# PATA_Breakout_Sequencer.net
KiCad netlist of a schematic drawn in EAGLE
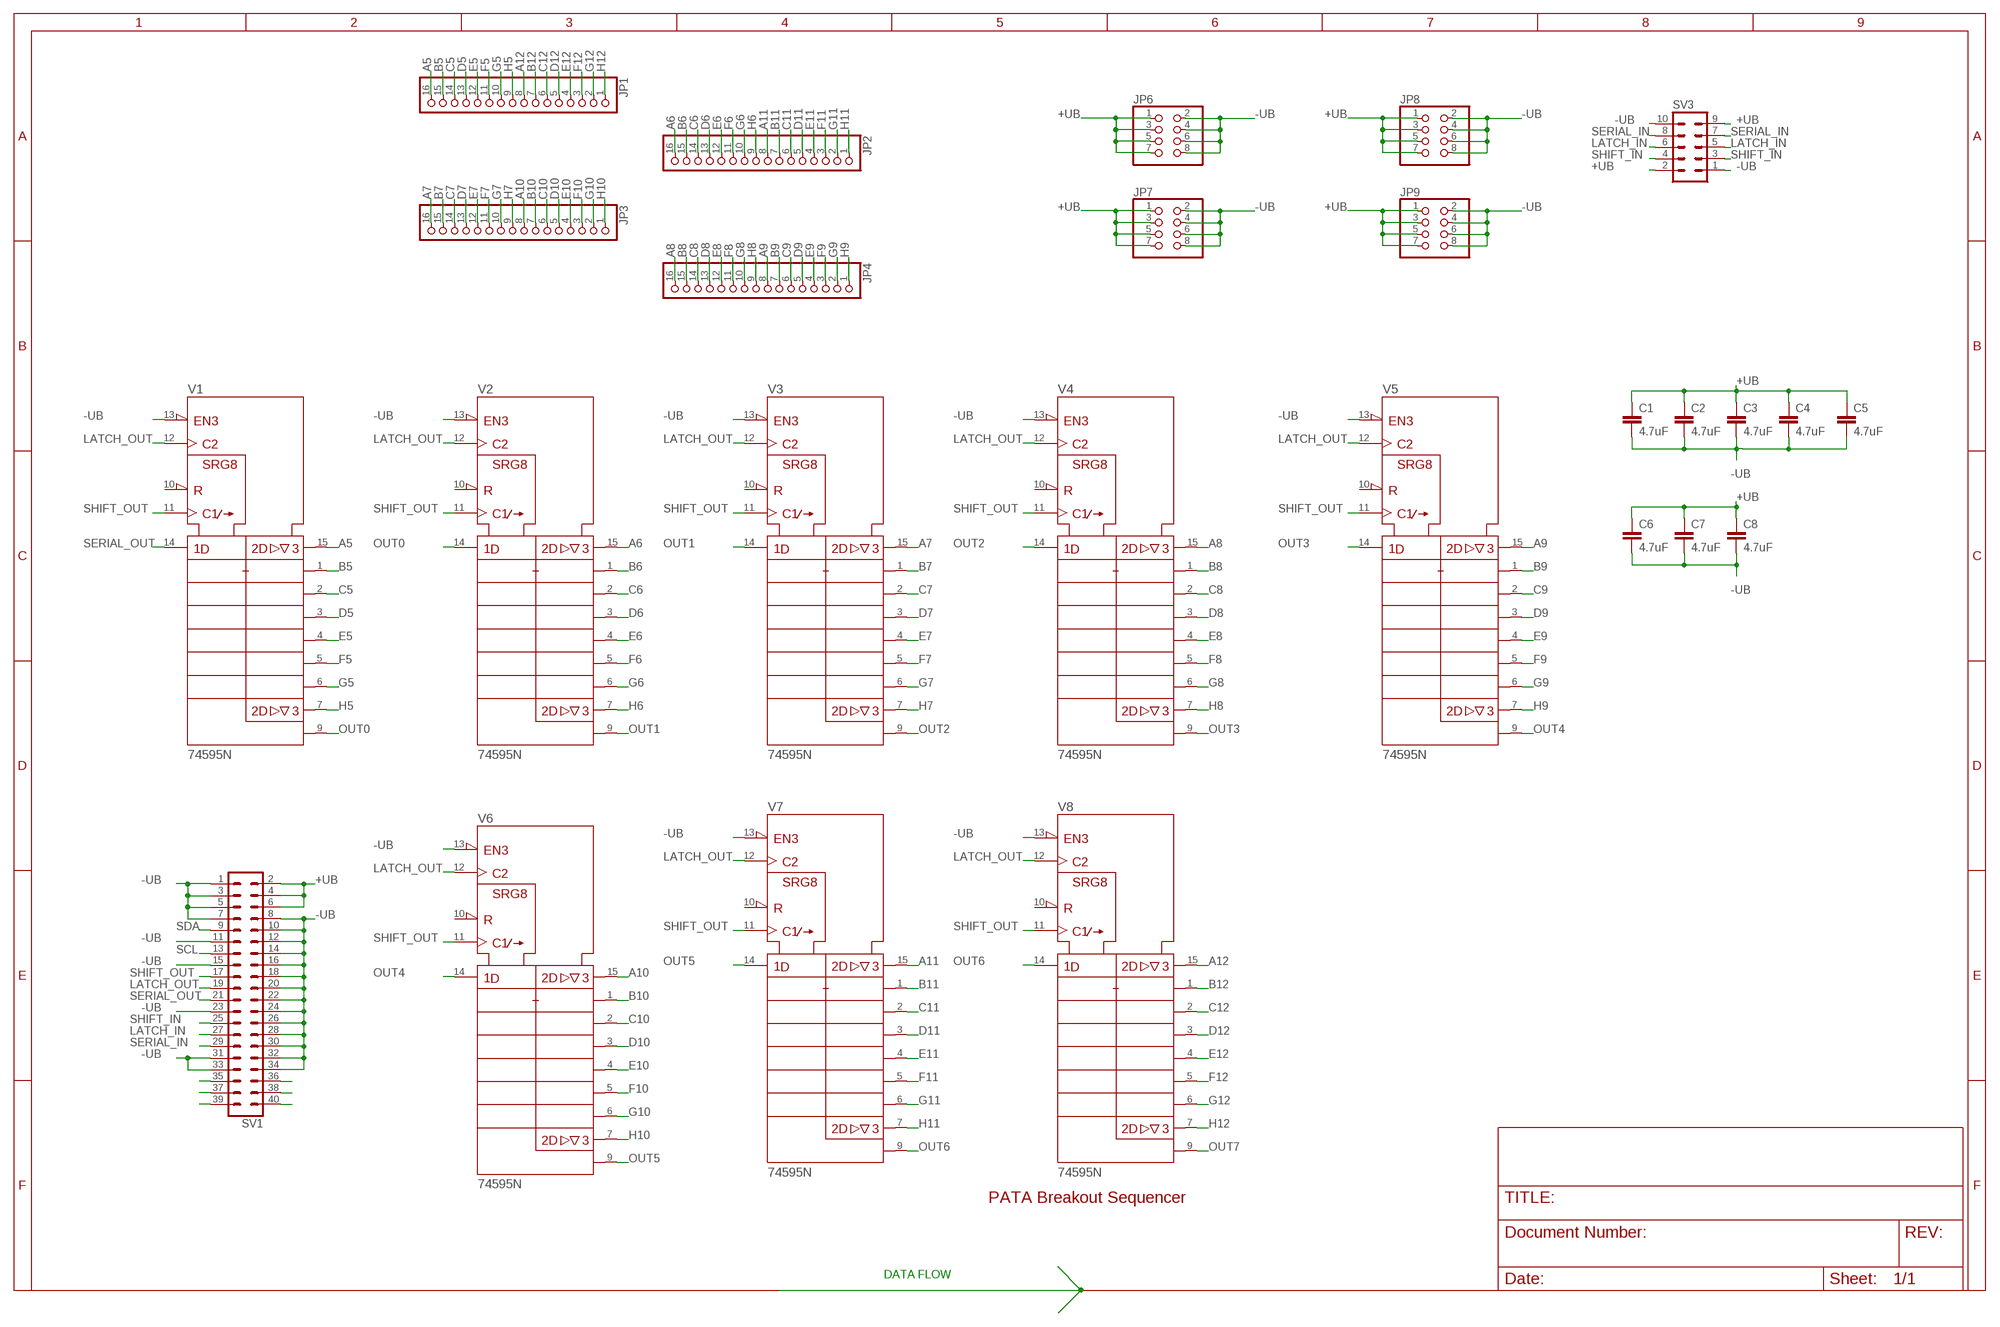
[diagram p0: schematic, sheet 1]

(export (version "E")
  (design (tool "Eeschema 10.0.6"))
  (components
    (comp (ref "C1")
      (value "4.7uF")
      (footprint "eagle-import:C050-024X044")
      (libsource (lib "eagle-import") (part "C-EU050-024X044"))
    )
    (comp (ref "C2")
      (value "4.7uF")
      (footprint "eagle-import:C050-024X044")
      (libsource (lib "eagle-import") (part "C-EU050-024X044"))
    )
    (comp (ref "C3")
      (value "4.7uF")
      (footprint "eagle-import:C050-024X044")
      (libsource (lib "eagle-import") (part "C-EU050-024X044"))
    )
    (comp (ref "C4")
      (value "4.7uF")
      (footprint "eagle-import:C050-024X044")
      (libsource (lib "eagle-import") (part "C-EU050-024X044"))
    )
    (comp (ref "C5")
      (value "4.7uF")
      (footprint "eagle-import:C050-024X044")
      (libsource (lib "eagle-import") (part "C-EU050-024X044"))
    )
    (comp (ref "C6")
      (value "4.7uF")
      (footprint "eagle-import:C050-024X044")
      (libsource (lib "eagle-import") (part "C-EU050-024X044"))
    )
    (comp (ref "C7")
      (value "4.7uF")
      (footprint "eagle-import:C050-024X044")
      (libsource (lib "eagle-import") (part "C-EU050-024X044"))
    )
    (comp (ref "C8")
      (value "4.7uF")
      (footprint "eagle-import:C050-024X044")
      (libsource (lib "eagle-import") (part "C-EU050-024X044"))
    )
    (comp (ref "JP1")
      (value "PINHD-1X16")
      (footprint "eagle-import:1X16")
      (libsource (lib "eagle-import") (part "PINHD-1X16"))
    )
    (comp (ref "JP2")
      (value "PINHD-1X16")
      (footprint "eagle-import:1X16")
      (libsource (lib "eagle-import") (part "PINHD-1X16"))
    )
    (comp (ref "JP3")
      (value "PINHD-1X16")
      (footprint "eagle-import:1X16")
      (libsource (lib "eagle-import") (part "PINHD-1X16"))
    )
    (comp (ref "JP4")
      (value "PINHD-1X16")
      (footprint "eagle-import:1X16")
      (libsource (lib "eagle-import") (part "PINHD-1X16"))
    )
    (comp (ref "JP6")
      (value "PINHD-2X4")
      (footprint "eagle-import:2X04")
      (libsource (lib "eagle-import") (part "PINHD-2X4"))
    )
    (comp (ref "JP7")
      (value "PINHD-2X4")
      (footprint "eagle-import:2X04")
      (libsource (lib "eagle-import") (part "PINHD-2X4"))
    )
    (comp (ref "JP8")
      (value "PINHD-2X4")
      (footprint "eagle-import:2X04")
      (libsource (lib "eagle-import") (part "PINHD-2X4"))
    )
    (comp (ref "JP9")
      (value "PINHD-2X4")
      (footprint "eagle-import:2X04")
      (libsource (lib "eagle-import") (part "PINHD-2X4"))
    )
    (comp (ref "SV1")
      (value "MA20-2")
      (footprint "eagle-import:MA20-2")
      (libsource (lib "eagle-import") (part "MA20-2"))
    )
    (comp (ref "SV3")
      (value "MA05-2")
      (footprint "eagle-import:MA05-2")
      (libsource (lib "eagle-import") (part "MA05-2"))
    )
    (comp (ref "V1")
      (value "74595N")
      (footprint "eagle-import:DIL16")
      (libsource (lib "eagle-import") (part "74595N"))
    )
    (comp (ref "V2")
      (value "74595N")
      (footprint "eagle-import:DIL16")
      (libsource (lib "eagle-import") (part "74595N"))
    )
    (comp (ref "V3")
      (value "74595N")
      (footprint "eagle-import:DIL16")
      (libsource (lib "eagle-import") (part "74595N"))
    )
    (comp (ref "V4")
      (value "74595N")
      (footprint "eagle-import:DIL16")
      (libsource (lib "eagle-import") (part "74595N"))
    )
    (comp (ref "V5")
      (value "74595N")
      (footprint "eagle-import:DIL16")
      (libsource (lib "eagle-import") (part "74595N"))
    )
    (comp (ref "V6")
      (value "74595N")
      (footprint "eagle-import:DIL16")
      (libsource (lib "eagle-import") (part "74595N"))
    )
    (comp (ref "V7")
      (value "74595N")
      (footprint "eagle-import:DIL16")
      (libsource (lib "eagle-import") (part "74595N"))
    )
    (comp (ref "V8")
      (value "74595N")
      (footprint "eagle-import:DIL16")
      (libsource (lib "eagle-import") (part "74595N"))
    )
  )
  (nets
    (net (code "1") (name "/+UB") (class "Default")
      (node (ref "C1") (pin "1") (pinfunction "1_1") (pintype "passive"))
      (node (ref "C2") (pin "1") (pinfunction "1_1") (pintype "passive"))
      (node (ref "C3") (pin "1") (pinfunction "1_1") (pintype "passive"))
      (node (ref "C4") (pin "1") (pinfunction "1_1") (pintype "passive"))
      (node (ref "C5") (pin "1") (pinfunction "1_1") (pintype "passive"))
      (node (ref "C6") (pin "1") (pinfunction "1_1") (pintype "passive"))
      (node (ref "C7") (pin "1") (pinfunction "1_1") (pintype "passive"))
      (node (ref "C8") (pin "1") (pinfunction "1_1") (pintype "passive"))
      (node (ref "JP6") (pin "1") (pinfunction "1_1") (pintype "passive"))
      (node (ref "JP6") (pin "3") (pinfunction "3_3") (pintype "passive"))
      (node (ref "JP6") (pin "5") (pinfunction "5_5") (pintype "passive"))
      (node (ref "JP6") (pin "7") (pinfunction "7_7") (pintype "passive"))
      (node (ref "JP7") (pin "1") (pinfunction "1_1") (pintype "passive"))
      (node (ref "JP7") (pin "3") (pinfunction "3_3") (pintype "passive"))
      (node (ref "JP7") (pin "5") (pinfunction "5_5") (pintype "passive"))
      (node (ref "JP7") (pin "7") (pinfunction "7_7") (pintype "passive"))
      (node (ref "JP8") (pin "1") (pinfunction "1_1") (pintype "passive"))
      (node (ref "JP8") (pin "3") (pinfunction "3_3") (pintype "passive"))
      (node (ref "JP8") (pin "5") (pinfunction "5_5") (pintype "passive"))
      (node (ref "JP8") (pin "7") (pinfunction "7_7") (pintype "passive"))
      (node (ref "JP9") (pin "1") (pinfunction "1_1") (pintype "passive"))
      (node (ref "JP9") (pin "3") (pinfunction "3_3") (pintype "passive"))
      (node (ref "JP9") (pin "5") (pinfunction "5_5") (pintype "passive"))
      (node (ref "JP9") (pin "7") (pinfunction "7_7") (pintype "passive"))
      (node (ref "SV1") (pin "2") (pinfunction "2_2") (pintype "passive"))
      (node (ref "SV1") (pin "4") (pinfunction "4_4") (pintype "passive"))
      (node (ref "SV1") (pin "6") (pinfunction "6_6") (pintype "passive"))
      (node (ref "SV3") (pin "2") (pinfunction "2_2") (pintype "passive"))
      (node (ref "SV3") (pin "9") (pinfunction "9_9") (pintype "passive"))
    )
    (net (code "2") (name "/-UB") (class "Default")
      (node (ref "C1") (pin "2") (pinfunction "2_2") (pintype "passive"))
      (node (ref "C2") (pin "2") (pinfunction "2_2") (pintype "passive"))
      (node (ref "C3") (pin "2") (pinfunction "2_2") (pintype "passive"))
      (node (ref "C4") (pin "2") (pinfunction "2_2") (pintype "passive"))
      (node (ref "C5") (pin "2") (pinfunction "2_2") (pintype "passive"))
      (node (ref "C6") (pin "2") (pinfunction "2_2") (pintype "passive"))
      (node (ref "C7") (pin "2") (pinfunction "2_2") (pintype "passive"))
      (node (ref "C8") (pin "2") (pinfunction "2_2") (pintype "passive"))
      (node (ref "JP6") (pin "2") (pinfunction "2_2") (pintype "passive"))
      (node (ref "JP6") (pin "4") (pinfunction "4_4") (pintype "passive"))
      (node (ref "JP6") (pin "6") (pinfunction "6_6") (pintype "passive"))
      (node (ref "JP6") (pin "8") (pinfunction "8_8") (pintype "passive"))
      (node (ref "JP7") (pin "2") (pinfunction "2_2") (pintype "passive"))
      (node (ref "JP7") (pin "4") (pinfunction "4_4") (pintype "passive"))
      (node (ref "JP7") (pin "6") (pinfunction "6_6") (pintype "passive"))
      (node (ref "JP7") (pin "8") (pinfunction "8_8") (pintype "passive"))
      (node (ref "JP8") (pin "2") (pinfunction "2_2") (pintype "passive"))
      (node (ref "JP8") (pin "4") (pinfunction "4_4") (pintype "passive"))
      (node (ref "JP8") (pin "6") (pinfunction "6_6") (pintype "passive"))
      (node (ref "JP8") (pin "8") (pinfunction "8_8") (pintype "passive"))
      (node (ref "JP9") (pin "2") (pinfunction "2_2") (pintype "passive"))
      (node (ref "JP9") (pin "4") (pinfunction "4_4") (pintype "passive"))
      (node (ref "JP9") (pin "6") (pinfunction "6_6") (pintype "passive"))
      (node (ref "JP9") (pin "8") (pinfunction "8_8") (pintype "passive"))
      (node (ref "SV1") (pin "1") (pinfunction "1_1") (pintype "passive"))
      (node (ref "SV1") (pin "10") (pinfunction "10_10") (pintype "passive"))
      (node (ref "SV1") (pin "11") (pinfunction "11_11") (pintype "passive"))
      (node (ref "SV1") (pin "12") (pinfunction "12_12") (pintype "passive"))
      (node (ref "SV1") (pin "14") (pinfunction "14_14") (pintype "passive"))
      (node (ref "SV1") (pin "15") (pinfunction "15_15") (pintype "passive"))
      (node (ref "SV1") (pin "16") (pinfunction "16_16") (pintype "passive"))
      (node (ref "SV1") (pin "18") (pinfunction "18_18") (pintype "passive"))
      (node (ref "SV1") (pin "20") (pinfunction "20_20") (pintype "passive"))
      (node (ref "SV1") (pin "22") (pinfunction "22_22") (pintype "passive"))
      (node (ref "SV1") (pin "23") (pinfunction "23_23") (pintype "passive"))
      (node (ref "SV1") (pin "24") (pinfunction "24_24") (pintype "passive"))
      (node (ref "SV1") (pin "26") (pinfunction "26_26") (pintype "passive"))
      (node (ref "SV1") (pin "28") (pinfunction "28_28") (pintype "passive"))
      (node (ref "SV1") (pin "3") (pinfunction "3_3") (pintype "passive"))
      (node (ref "SV1") (pin "30") (pinfunction "30_30") (pintype "passive"))
      (node (ref "SV1") (pin "31") (pinfunction "31_31") (pintype "passive"))
      (node (ref "SV1") (pin "32") (pinfunction "32_32") (pintype "passive"))
      (node (ref "SV1") (pin "33") (pinfunction "33_33") (pintype "passive"))
      (node (ref "SV1") (pin "34") (pinfunction "34_34") (pintype "passive"))
      (node (ref "SV1") (pin "5") (pinfunction "5_5") (pintype "passive"))
      (node (ref "SV1") (pin "7") (pinfunction "7_7") (pintype "passive"))
      (node (ref "SV1") (pin "8") (pinfunction "8_8") (pintype "passive"))
      (node (ref "SV3") (pin "1") (pinfunction "1_1") (pintype "passive"))
      (node (ref "SV3") (pin "10") (pinfunction "10_10") (pintype "passive"))
      (node (ref "V1") (pin "13") (pinfunction "~{G}_13") (pintype "input"))
      (node (ref "V2") (pin "13") (pinfunction "~{G}_13") (pintype "input"))
      (node (ref "V3") (pin "13") (pinfunction "~{G}_13") (pintype "input"))
      (node (ref "V4") (pin "13") (pinfunction "~{G}_13") (pintype "input"))
      (node (ref "V5") (pin "13") (pinfunction "~{G}_13") (pintype "input"))
      (node (ref "V6") (pin "13") (pinfunction "~{G}_13") (pintype "input"))
      (node (ref "V7") (pin "13") (pinfunction "~{G}_13") (pintype "input"))
      (node (ref "V8") (pin "13") (pinfunction "~{G}_13") (pintype "input"))
    )
    (net (code "3") (name "/A5") (class "Default")
      (node (ref "JP1") (pin "16") (pinfunction "16_16") (pintype "passive"))
      (node (ref "V1") (pin "15") (pinfunction "QA_15") (pintype "tri_state"))
    )
    (net (code "4") (name "/A6") (class "Default")
      (node (ref "JP2") (pin "16") (pinfunction "16_16") (pintype "passive"))
      (node (ref "V2") (pin "15") (pinfunction "QA_15") (pintype "tri_state"))
    )
    (net (code "5") (name "/A7") (class "Default")
      (node (ref "JP3") (pin "16") (pinfunction "16_16") (pintype "passive"))
      (node (ref "V3") (pin "15") (pinfunction "QA_15") (pintype "tri_state"))
    )
    (net (code "6") (name "/A8") (class "Default")
      (node (ref "JP4") (pin "16") (pinfunction "16_16") (pintype "passive"))
      (node (ref "V4") (pin "15") (pinfunction "QA_15") (pintype "tri_state"))
    )
    (net (code "7") (name "/A9") (class "Default")
      (node (ref "JP4") (pin "8") (pinfunction "8_8") (pintype "passive"))
      (node (ref "V5") (pin "15") (pinfunction "QA_15") (pintype "tri_state"))
    )
    (net (code "8") (name "/A10") (class "Default")
      (node (ref "JP3") (pin "8") (pinfunction "8_8") (pintype "passive"))
      (node (ref "V6") (pin "15") (pinfunction "QA_15") (pintype "tri_state"))
    )
    (net (code "9") (name "/A11") (class "Default")
      (node (ref "JP2") (pin "8") (pinfunction "8_8") (pintype "passive"))
      (node (ref "V7") (pin "15") (pinfunction "QA_15") (pintype "tri_state"))
    )
    (net (code "10") (name "/A12") (class "Default")
      (node (ref "JP1") (pin "8") (pinfunction "8_8") (pintype "passive"))
      (node (ref "V8") (pin "15") (pinfunction "QA_15") (pintype "tri_state"))
    )
    (net (code "11") (name "/B5") (class "Default")
      (node (ref "JP1") (pin "15") (pinfunction "15_15") (pintype "passive"))
      (node (ref "V1") (pin "1") (pinfunction "QB_1") (pintype "tri_state"))
    )
    (net (code "12") (name "/B6") (class "Default")
      (node (ref "JP2") (pin "15") (pinfunction "15_15") (pintype "passive"))
      (node (ref "V2") (pin "1") (pinfunction "QB_1") (pintype "tri_state"))
    )
    (net (code "13") (name "/B7") (class "Default")
      (node (ref "JP3") (pin "15") (pinfunction "15_15") (pintype "passive"))
      (node (ref "V3") (pin "1") (pinfunction "QB_1") (pintype "tri_state"))
    )
    (net (code "14") (name "/B8") (class "Default")
      (node (ref "JP4") (pin "15") (pinfunction "15_15") (pintype "passive"))
      (node (ref "V4") (pin "1") (pinfunction "QB_1") (pintype "tri_state"))
    )
    (net (code "15") (name "/B9") (class "Default")
      (node (ref "JP4") (pin "7") (pinfunction "7_7") (pintype "passive"))
      (node (ref "V5") (pin "1") (pinfunction "QB_1") (pintype "tri_state"))
    )
    (net (code "16") (name "/B10") (class "Default")
      (node (ref "JP3") (pin "7") (pinfunction "7_7") (pintype "passive"))
      (node (ref "V6") (pin "1") (pinfunction "QB_1") (pintype "tri_state"))
    )
    (net (code "17") (name "/B11") (class "Default")
      (node (ref "JP2") (pin "7") (pinfunction "7_7") (pintype "passive"))
      (node (ref "V7") (pin "1") (pinfunction "QB_1") (pintype "tri_state"))
    )
    (net (code "18") (name "/B12") (class "Default")
      (node (ref "JP1") (pin "7") (pinfunction "7_7") (pintype "passive"))
      (node (ref "V8") (pin "1") (pinfunction "QB_1") (pintype "tri_state"))
    )
    (net (code "19") (name "/C5") (class "Default")
      (node (ref "JP1") (pin "14") (pinfunction "14_14") (pintype "passive"))
      (node (ref "V1") (pin "2") (pinfunction "QC_2") (pintype "tri_state"))
    )
    (net (code "20") (name "/C6") (class "Default")
      (node (ref "JP2") (pin "14") (pinfunction "14_14") (pintype "passive"))
      (node (ref "V2") (pin "2") (pinfunction "QC_2") (pintype "tri_state"))
    )
    (net (code "21") (name "/C7") (class "Default")
      (node (ref "JP3") (pin "14") (pinfunction "14_14") (pintype "passive"))
      (node (ref "V3") (pin "2") (pinfunction "QC_2") (pintype "tri_state"))
    )
    (net (code "22") (name "/C8") (class "Default")
      (node (ref "JP4") (pin "14") (pinfunction "14_14") (pintype "passive"))
      (node (ref "V4") (pin "2") (pinfunction "QC_2") (pintype "tri_state"))
    )
    (net (code "23") (name "/C9") (class "Default")
      (node (ref "JP4") (pin "6") (pinfunction "6_6") (pintype "passive"))
      (node (ref "V5") (pin "2") (pinfunction "QC_2") (pintype "tri_state"))
    )
    (net (code "24") (name "/C10") (class "Default")
      (node (ref "JP3") (pin "6") (pinfunction "6_6") (pintype "passive"))
      (node (ref "V6") (pin "2") (pinfunction "QC_2") (pintype "tri_state"))
    )
    (net (code "25") (name "/C11") (class "Default")
      (node (ref "JP2") (pin "6") (pinfunction "6_6") (pintype "passive"))
      (node (ref "V7") (pin "2") (pinfunction "QC_2") (pintype "tri_state"))
    )
    (net (code "26") (name "/C12") (class "Default")
      (node (ref "JP1") (pin "6") (pinfunction "6_6") (pintype "passive"))
      (node (ref "V8") (pin "2") (pinfunction "QC_2") (pintype "tri_state"))
    )
    (net (code "27") (name "/D5") (class "Default")
      (node (ref "JP1") (pin "13") (pinfunction "13_13") (pintype "passive"))
      (node (ref "V1") (pin "3") (pinfunction "QD_3") (pintype "tri_state"))
    )
    (net (code "28") (name "/D6") (class "Default")
      (node (ref "JP2") (pin "13") (pinfunction "13_13") (pintype "passive"))
      (node (ref "V2") (pin "3") (pinfunction "QD_3") (pintype "tri_state"))
    )
    (net (code "29") (name "/D7") (class "Default")
      (node (ref "JP3") (pin "13") (pinfunction "13_13") (pintype "passive"))
      (node (ref "V3") (pin "3") (pinfunction "QD_3") (pintype "tri_state"))
    )
    (net (code "30") (name "/D8") (class "Default")
      (node (ref "JP4") (pin "13") (pinfunction "13_13") (pintype "passive"))
      (node (ref "V4") (pin "3") (pinfunction "QD_3") (pintype "tri_state"))
    )
    (net (code "31") (name "/D9") (class "Default")
      (node (ref "JP4") (pin "5") (pinfunction "5_5") (pintype "passive"))
      (node (ref "V5") (pin "3") (pinfunction "QD_3") (pintype "tri_state"))
    )
    (net (code "32") (name "/D10") (class "Default")
      (node (ref "JP3") (pin "5") (pinfunction "5_5") (pintype "passive"))
      (node (ref "V6") (pin "3") (pinfunction "QD_3") (pintype "tri_state"))
    )
    (net (code "33") (name "/D11") (class "Default")
      (node (ref "JP2") (pin "5") (pinfunction "5_5") (pintype "passive"))
      (node (ref "V7") (pin "3") (pinfunction "QD_3") (pintype "tri_state"))
    )
    (net (code "34") (name "/D12") (class "Default")
      (node (ref "JP1") (pin "5") (pinfunction "5_5") (pintype "passive"))
      (node (ref "V8") (pin "3") (pinfunction "QD_3") (pintype "tri_state"))
    )
    (net (code "35") (name "/E5") (class "Default")
      (node (ref "JP1") (pin "12") (pinfunction "12_12") (pintype "passive"))
      (node (ref "V1") (pin "4") (pinfunction "QE_4") (pintype "tri_state"))
    )
    (net (code "36") (name "/E6") (class "Default")
      (node (ref "JP2") (pin "12") (pinfunction "12_12") (pintype "passive"))
      (node (ref "V2") (pin "4") (pinfunction "QE_4") (pintype "tri_state"))
    )
    (net (code "37") (name "/E7") (class "Default")
      (node (ref "JP3") (pin "12") (pinfunction "12_12") (pintype "passive"))
      (node (ref "V3") (pin "4") (pinfunction "QE_4") (pintype "tri_state"))
    )
    (net (code "38") (name "/E8") (class "Default")
      (node (ref "JP4") (pin "12") (pinfunction "12_12") (pintype "passive"))
      (node (ref "V4") (pin "4") (pinfunction "QE_4") (pintype "tri_state"))
    )
    (net (code "39") (name "/E9") (class "Default")
      (node (ref "JP4") (pin "4") (pinfunction "4_4") (pintype "passive"))
      (node (ref "V5") (pin "4") (pinfunction "QE_4") (pintype "tri_state"))
    )
    (net (code "40") (name "/E10") (class "Default")
      (node (ref "JP3") (pin "4") (pinfunction "4_4") (pintype "passive"))
      (node (ref "V6") (pin "4") (pinfunction "QE_4") (pintype "tri_state"))
    )
    (net (code "41") (name "/E11") (class "Default")
      (node (ref "JP2") (pin "4") (pinfunction "4_4") (pintype "passive"))
      (node (ref "V7") (pin "4") (pinfunction "QE_4") (pintype "tri_state"))
    )
    (net (code "42") (name "/E12") (class "Default")
      (node (ref "JP1") (pin "4") (pinfunction "4_4") (pintype "passive"))
      (node (ref "V8") (pin "4") (pinfunction "QE_4") (pintype "tri_state"))
    )
    (net (code "43") (name "/F5") (class "Default")
      (node (ref "JP1") (pin "11") (pinfunction "11_11") (pintype "passive"))
      (node (ref "V1") (pin "5") (pinfunction "QF_5") (pintype "tri_state"))
    )
    (net (code "44") (name "/F6") (class "Default")
      (node (ref "JP2") (pin "11") (pinfunction "11_11") (pintype "passive"))
      (node (ref "V2") (pin "5") (pinfunction "QF_5") (pintype "tri_state"))
    )
    (net (code "45") (name "/F7") (class "Default")
      (node (ref "JP3") (pin "11") (pinfunction "11_11") (pintype "passive"))
      (node (ref "V3") (pin "5") (pinfunction "QF_5") (pintype "tri_state"))
    )
    (net (code "46") (name "/F8") (class "Default")
      (node (ref "JP4") (pin "11") (pinfunction "11_11") (pintype "passive"))
      (node (ref "V4") (pin "5") (pinfunction "QF_5") (pintype "tri_state"))
    )
    (net (code "47") (name "/F9") (class "Default")
      (node (ref "JP4") (pin "3") (pinfunction "3_3") (pintype "passive"))
      (node (ref "V5") (pin "5") (pinfunction "QF_5") (pintype "tri_state"))
    )
    (net (code "48") (name "/F10") (class "Default")
      (node (ref "JP3") (pin "3") (pinfunction "3_3") (pintype "passive"))
      (node (ref "V6") (pin "5") (pinfunction "QF_5") (pintype "tri_state"))
    )
    (net (code "49") (name "/F11") (class "Default")
      (node (ref "JP2") (pin "3") (pinfunction "3_3") (pintype "passive"))
      (node (ref "V7") (pin "5") (pinfunction "QF_5") (pintype "tri_state"))
    )
    (net (code "50") (name "/F12") (class "Default")
      (node (ref "JP1") (pin "3") (pinfunction "3_3") (pintype "passive"))
      (node (ref "V8") (pin "5") (pinfunction "QF_5") (pintype "tri_state"))
    )
    (net (code "51") (name "/G5") (class "Default")
      (node (ref "JP1") (pin "10") (pinfunction "10_10") (pintype "passive"))
      (node (ref "V1") (pin "6") (pinfunction "QG_6") (pintype "tri_state"))
    )
    (net (code "52") (name "/G6") (class "Default")
      (node (ref "JP2") (pin "10") (pinfunction "10_10") (pintype "passive"))
      (node (ref "V2") (pin "6") (pinfunction "QG_6") (pintype "tri_state"))
    )
    (net (code "53") (name "/G7") (class "Default")
      (node (ref "JP3") (pin "10") (pinfunction "10_10") (pintype "passive"))
      (node (ref "V3") (pin "6") (pinfunction "QG_6") (pintype "tri_state"))
    )
    (net (code "54") (name "/G8") (class "Default")
      (node (ref "JP4") (pin "10") (pinfunction "10_10") (pintype "passive"))
      (node (ref "V4") (pin "6") (pinfunction "QG_6") (pintype "tri_state"))
    )
    (net (code "55") (name "/G9") (class "Default")
      (node (ref "JP4") (pin "2") (pinfunction "2_2") (pintype "passive"))
      (node (ref "V5") (pin "6") (pinfunction "QG_6") (pintype "tri_state"))
    )
    (net (code "56") (name "/G10") (class "Default")
      (node (ref "JP3") (pin "2") (pinfunction "2_2") (pintype "passive"))
      (node (ref "V6") (pin "6") (pinfunction "QG_6") (pintype "tri_state"))
    )
    (net (code "57") (name "/G11") (class "Default")
      (node (ref "JP2") (pin "2") (pinfunction "2_2") (pintype "passive"))
      (node (ref "V7") (pin "6") (pinfunction "QG_6") (pintype "tri_state"))
    )
    (net (code "58") (name "/G12") (class "Default")
      (node (ref "JP1") (pin "2") (pinfunction "2_2") (pintype "passive"))
      (node (ref "V8") (pin "6") (pinfunction "QG_6") (pintype "tri_state"))
    )
    (net (code "59") (name "/H5") (class "Default")
      (node (ref "JP1") (pin "9") (pinfunction "9_9") (pintype "passive"))
      (node (ref "V1") (pin "7") (pinfunction "QH_7") (pintype "tri_state"))
    )
    (net (code "60") (name "/H6") (class "Default")
      (node (ref "JP2") (pin "9") (pinfunction "9_9") (pintype "passive"))
      (node (ref "V2") (pin "7") (pinfunction "QH_7") (pintype "tri_state"))
    )
    (net (code "61") (name "/H7") (class "Default")
      (node (ref "JP3") (pin "9") (pinfunction "9_9") (pintype "passive"))
      (node (ref "V3") (pin "7") (pinfunction "QH_7") (pintype "tri_state"))
    )
    (net (code "62") (name "/H8") (class "Default")
      (node (ref "JP4") (pin "9") (pinfunction "9_9") (pintype "passive"))
      (node (ref "V4") (pin "7") (pinfunction "QH_7") (pintype "tri_state"))
    )
    (net (code "63") (name "/H9") (class "Default")
      (node (ref "JP4") (pin "1") (pinfunction "1_1") (pintype "passive"))
      (node (ref "V5") (pin "7") (pinfunction "QH_7") (pintype "tri_state"))
    )
    (net (code "64") (name "/H10") (class "Default")
      (node (ref "JP3") (pin "1") (pinfunction "1_1") (pintype "passive"))
      (node (ref "V6") (pin "7") (pinfunction "QH_7") (pintype "tri_state"))
    )
    (net (code "65") (name "/H11") (class "Default")
      (node (ref "JP2") (pin "1") (pinfunction "1_1") (pintype "passive"))
      (node (ref "V7") (pin "7") (pinfunction "QH_7") (pintype "tri_state"))
    )
    (net (code "66") (name "/H12") (class "Default")
      (node (ref "JP1") (pin "1") (pinfunction "1_1") (pintype "passive"))
      (node (ref "V8") (pin "7") (pinfunction "QH_7") (pintype "tri_state"))
    )
    (net (code "67") (name "/LATCH_IN") (class "Default")
      (node (ref "SV1") (pin "27") (pinfunction "27_27") (pintype "passive"))
      (node (ref "SV3") (pin "5") (pinfunction "5_5") (pintype "passive"))
      (node (ref "SV3") (pin "6") (pinfunction "6_6") (pintype "passive"))
    )
    (net (code "68") (name "/LATCH_OUT") (class "Default")
      (node (ref "SV1") (pin "19") (pinfunction "19_19") (pintype "passive"))
      (node (ref "V1") (pin "12") (pinfunction "RCK_12") (pintype "input"))
      (node (ref "V2") (pin "12") (pinfunction "RCK_12") (pintype "input"))
      (node (ref "V3") (pin "12") (pinfunction "RCK_12") (pintype "input"))
      (node (ref "V4") (pin "12") (pinfunction "RCK_12") (pintype "input"))
      (node (ref "V5") (pin "12") (pinfunction "RCK_12") (pintype "input"))
      (node (ref "V6") (pin "12") (pinfunction "RCK_12") (pintype "input"))
      (node (ref "V7") (pin "12") (pinfunction "RCK_12") (pintype "input"))
      (node (ref "V8") (pin "12") (pinfunction "RCK_12") (pintype "input"))
    )
    (net (code "69") (name "/OUT0") (class "Default")
      (node (ref "V1") (pin "9") (pinfunction "QH*_9") (pintype "output"))
      (node (ref "V2") (pin "14") (pinfunction "SER_14") (pintype "input"))
    )
    (net (code "70") (name "/OUT1") (class "Default")
      (node (ref "V2") (pin "9") (pinfunction "QH*_9") (pintype "output"))
      (node (ref "V3") (pin "14") (pinfunction "SER_14") (pintype "input"))
    )
    (net (code "71") (name "/OUT2") (class "Default")
      (node (ref "V3") (pin "9") (pinfunction "QH*_9") (pintype "output"))
      (node (ref "V4") (pin "14") (pinfunction "SER_14") (pintype "input"))
    )
    (net (code "72") (name "/OUT3") (class "Default")
      (node (ref "V4") (pin "9") (pinfunction "QH*_9") (pintype "output"))
      (node (ref "V5") (pin "14") (pinfunction "SER_14") (pintype "input"))
    )
    (net (code "73") (name "/OUT4") (class "Default")
      (node (ref "V5") (pin "9") (pinfunction "QH*_9") (pintype "output"))
      (node (ref "V6") (pin "14") (pinfunction "SER_14") (pintype "input"))
    )
    (net (code "74") (name "/OUT5") (class "Default")
      (node (ref "V6") (pin "9") (pinfunction "QH*_9") (pintype "output"))
      (node (ref "V7") (pin "14") (pinfunction "SER_14") (pintype "input"))
    )
    (net (code "75") (name "/OUT6") (class "Default")
      (node (ref "V7") (pin "9") (pinfunction "QH*_9") (pintype "output"))
      (node (ref "V8") (pin "14") (pinfunction "SER_14") (pintype "input"))
    )
    (net (code "76") (name "/OUT7") (class "Default")
      (node (ref "V8") (pin "9") (pinfunction "QH*_9") (pintype "output"))
    )
    (net (code "77") (name "/SCL") (class "Default")
      (node (ref "SV1") (pin "13") (pinfunction "13_13") (pintype "passive"))
    )
    (net (code "78") (name "/SDA") (class "Default")
      (node (ref "SV1") (pin "9") (pinfunction "9_9") (pintype "passive"))
    )
    (net (code "79") (name "/SERIAL_IN") (class "Default")
      (node (ref "SV1") (pin "29") (pinfunction "29_29") (pintype "passive"))
      (node (ref "SV3") (pin "7") (pinfunction "7_7") (pintype "passive"))
      (node (ref "SV3") (pin "8") (pinfunction "8_8") (pintype "passive"))
    )
    (net (code "80") (name "/SERIAL_OUT") (class "Default")
      (node (ref "SV1") (pin "21") (pinfunction "21_21") (pintype "passive"))
      (node (ref "V1") (pin "14") (pinfunction "SER_14") (pintype "input"))
    )
    (net (code "81") (name "/SHIFT_IN") (class "Default")
      (node (ref "SV1") (pin "25") (pinfunction "25_25") (pintype "passive"))
      (node (ref "SV3") (pin "3") (pinfunction "3_3") (pintype "passive"))
      (node (ref "SV3") (pin "4") (pinfunction "4_4") (pintype "passive"))
    )
    (net (code "82") (name "/SHIFT_OUT") (class "Default")
      (node (ref "SV1") (pin "17") (pinfunction "17_17") (pintype "passive"))
      (node (ref "V1") (pin "11") (pinfunction "SRCK_11") (pintype "input"))
      (node (ref "V2") (pin "11") (pinfunction "SRCK_11") (pintype "input"))
      (node (ref "V3") (pin "11") (pinfunction "SRCK_11") (pintype "input"))
      (node (ref "V4") (pin "11") (pinfunction "SRCK_11") (pintype "input"))
      (node (ref "V5") (pin "11") (pinfunction "SRCK_11") (pintype "input"))
      (node (ref "V6") (pin "11") (pinfunction "SRCK_11") (pintype "input"))
      (node (ref "V7") (pin "11") (pinfunction "SRCK_11") (pintype "input"))
      (node (ref "V8") (pin "11") (pinfunction "SRCK_11") (pintype "input"))
    )
    (net (code "83") (name "unconnected-(SV1-Pad35)") (class "Default")
      (node (ref "SV1") (pin "35") (pinfunction "35_35") (pintype "passive"))
    )
    (net (code "84") (name "unconnected-(SV1-Pad36)") (class "Default")
      (node (ref "SV1") (pin "36") (pinfunction "36_36") (pintype "passive"))
    )
    (net (code "85") (name "unconnected-(SV1-Pad37)") (class "Default")
      (node (ref "SV1") (pin "37") (pinfunction "37_37") (pintype "passive"))
    )
    (net (code "86") (name "unconnected-(SV1-Pad38)") (class "Default")
      (node (ref "SV1") (pin "38") (pinfunction "38_38") (pintype "passive"))
    )
    (net (code "87") (name "unconnected-(SV1-Pad39)") (class "Default")
      (node (ref "SV1") (pin "39") (pinfunction "39_39") (pintype "passive"))
    )
    (net (code "88") (name "unconnected-(SV1-Pad40)") (class "Default")
      (node (ref "SV1") (pin "40") (pinfunction "40_40") (pintype "passive"))
    )
    (net (code "89") (name "unconnected-(V1C-~{SRCLR}-Pad10)") (class "Default")
      (node (ref "V1") (pin "10") (pinfunction "~{SRCLR}_10") (pintype "input"))
    )
    (net (code "90") (name "unconnected-(V2C-~{SRCLR}-Pad10)") (class "Default")
      (node (ref "V2") (pin "10") (pinfunction "~{SRCLR}_10") (pintype "input"))
    )
    (net (code "91") (name "unconnected-(V3C-~{SRCLR}-Pad10)") (class "Default")
      (node (ref "V3") (pin "10") (pinfunction "~{SRCLR}_10") (pintype "input"))
    )
    (net (code "92") (name "unconnected-(V4C-~{SRCLR}-Pad10)") (class "Default")
      (node (ref "V4") (pin "10") (pinfunction "~{SRCLR}_10") (pintype "input"))
    )
    (net (code "93") (name "unconnected-(V5C-~{SRCLR}-Pad10)") (class "Default")
      (node (ref "V5") (pin "10") (pinfunction "~{SRCLR}_10") (pintype "input"))
    )
    (net (code "94") (name "unconnected-(V6C-~{SRCLR}-Pad10)") (class "Default")
      (node (ref "V6") (pin "10") (pinfunction "~{SRCLR}_10") (pintype "input"))
    )
    (net (code "95") (name "unconnected-(V7C-~{SRCLR}-Pad10)") (class "Default")
      (node (ref "V7") (pin "10") (pinfunction "~{SRCLR}_10") (pintype "input"))
    )
    (net (code "96") (name "unconnected-(V8C-~{SRCLR}-Pad10)") (class "Default")
      (node (ref "V8") (pin "10") (pinfunction "~{SRCLR}_10") (pintype "input"))
    )
  )
)
